# MCUCircuit.net
KiCad netlist of a schematic drawn in Altium Designer
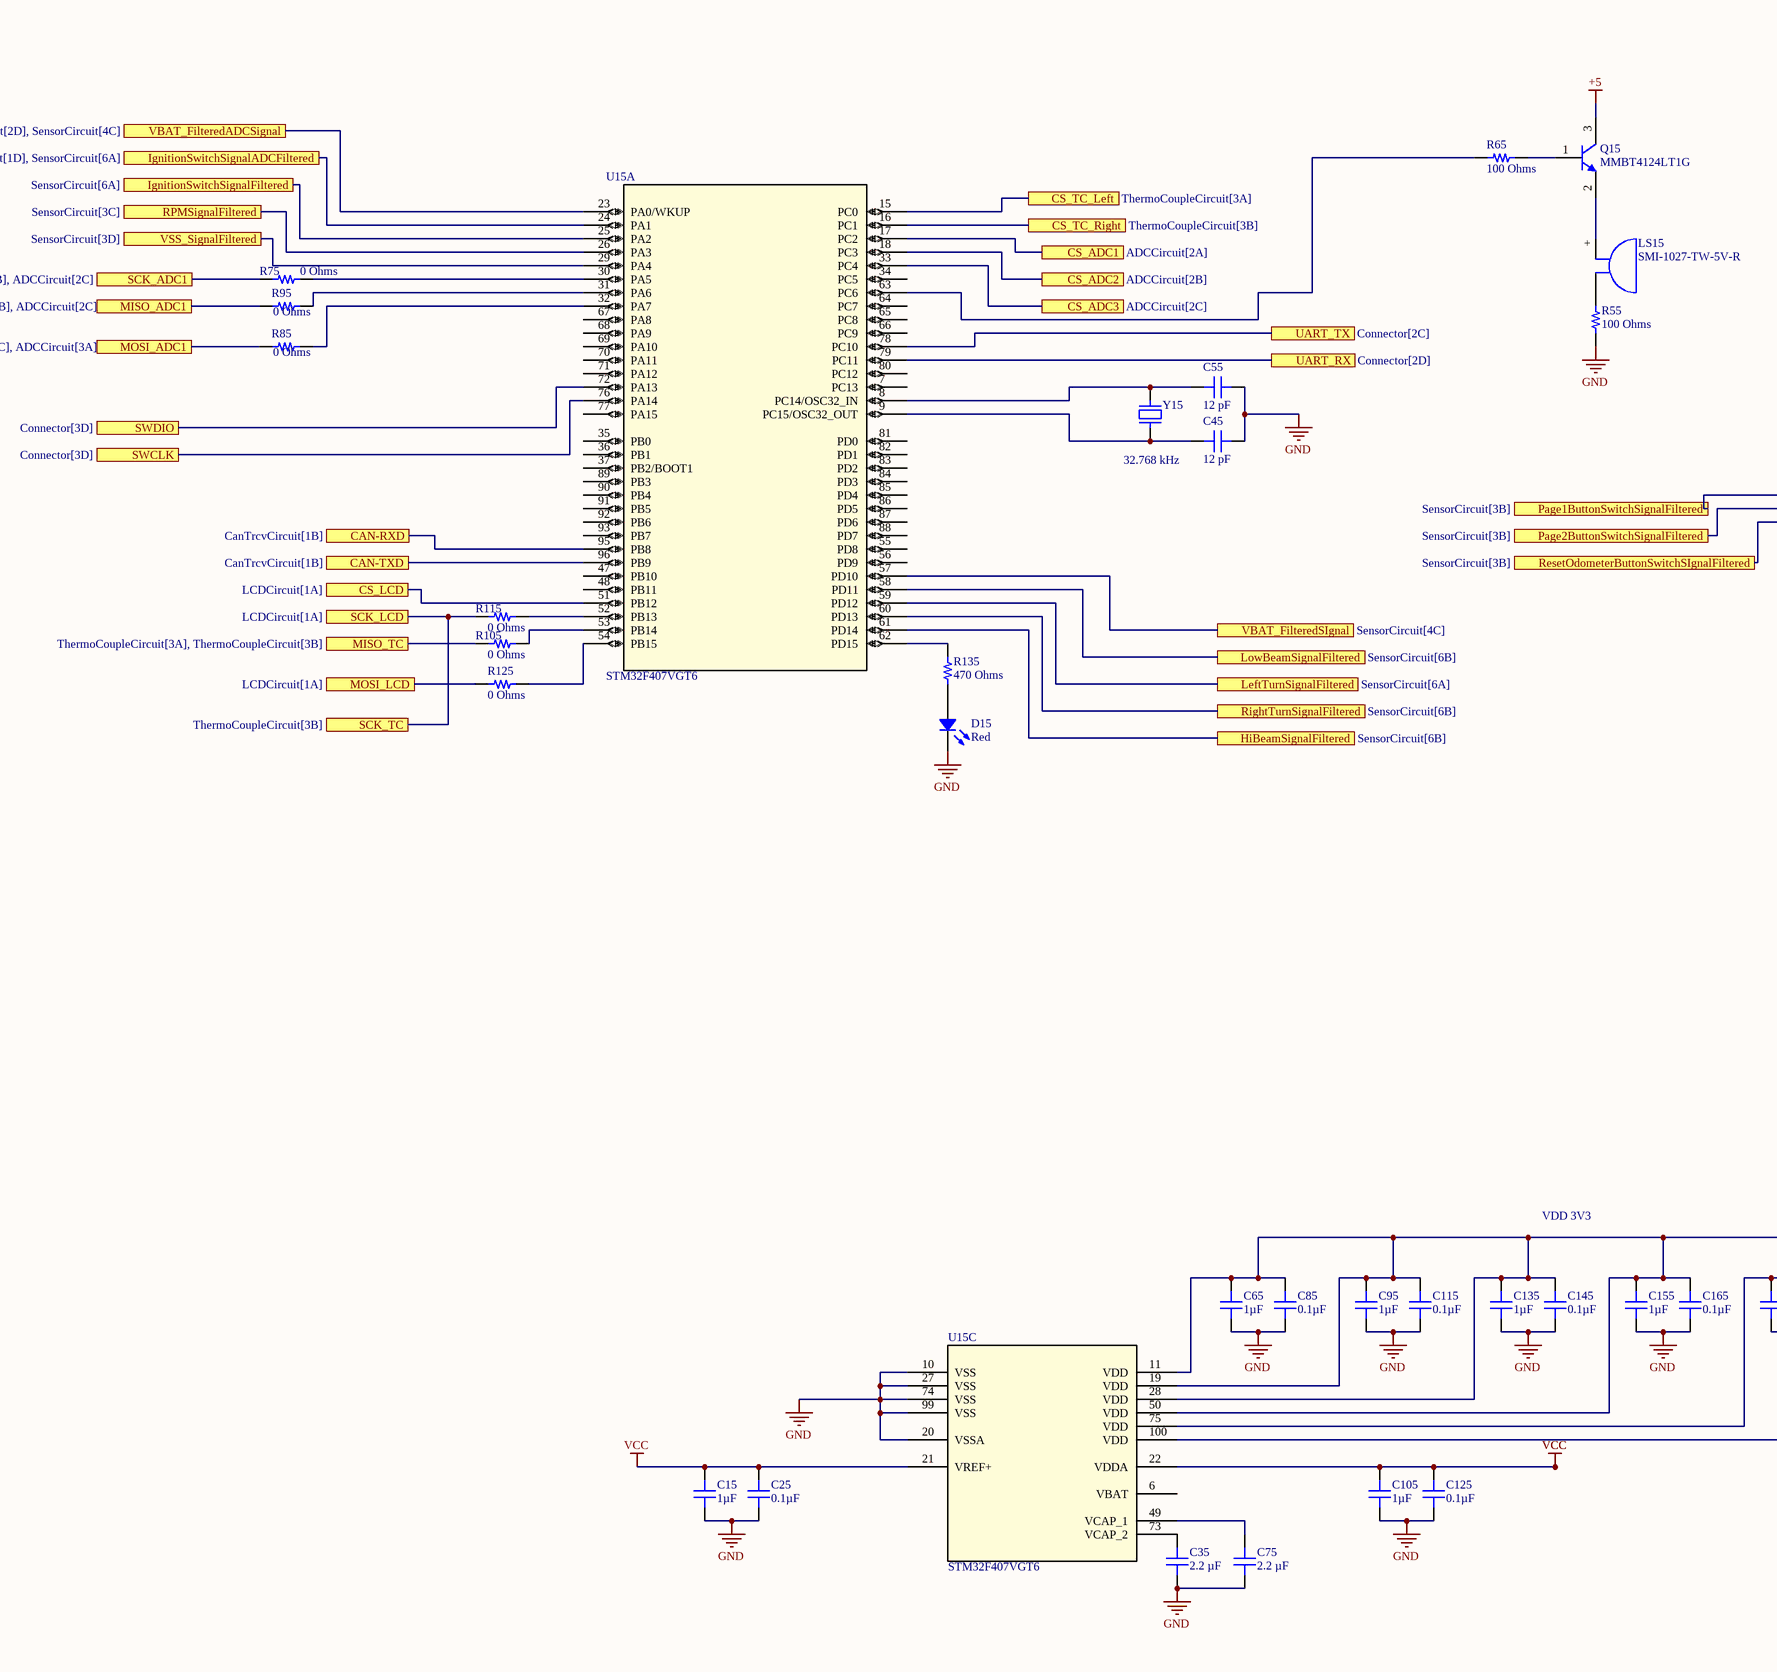
[diagram p0: MCUCircuit.SchDoc, left]
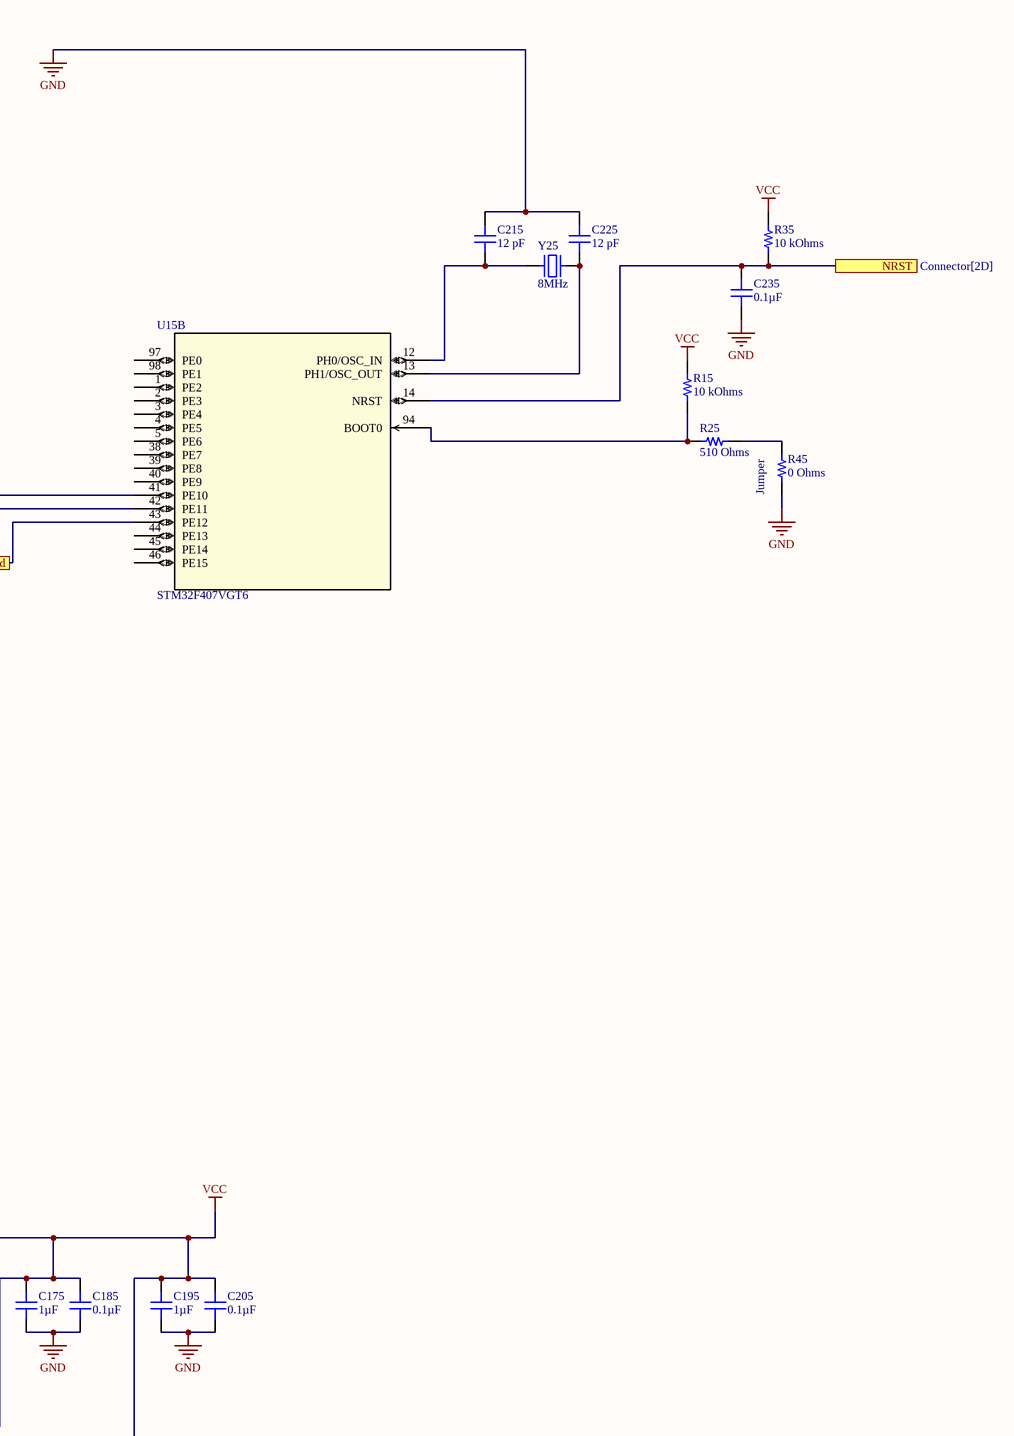
[diagram p1: MCUCircuit.SchDoc, right]

(export (version "E")
  (design (tool "Eeschema 10.0.6"))
  (components
    (comp (ref "C15")
      (value "1µF")
      (footprint "C0805")
      (description "CAP CER 1UF 6.3V X5R 0805")
      (fields (field (name "PART NUMBER") "LGC26D105MAT2S1") (field (name "MANUFACTURER") "AVX Corporation"))
      (libsource (lib "Celestial Altium Library - altium_library") (part "Capacitor"))
    )
    (comp (ref "C25")
      (value "0.1µF")
      (footprint "C0805")
      (description "CAP CER 0.1UF 6.3V X7R 0805")
      (fields (field (name "PART NUMBER") "08056C104JAZ2A") (field (name "MANUFACTURER") "AVX Corporation"))
      (libsource (lib "Celestial Altium Library - altium_library") (part "Capacitor"))
    )
    (comp (ref "C35")
      (value "2.2 µF")
      (footprint "C0805")
      (description "CAP CER 2.2UF 6.3V X5R 0805")
      (fields
        (field (name "PART NUMBER") "VJ0805G225KXYTW1BC")
        (field (name "MANUFACTURER") "Vishay Vitramon")
      )
      (libsource (lib "Celestial Altium Library - altium_library") (part "Capacitor"))
    )
    (comp (ref "C45")
      (value "12 pF")
      (footprint "C0805")
      (description "CAP CER 12PF 10V X8R 0805")
      (fields (field (name "PART NUMBER") "C0805C120J8HAC7800") (field (name "MANUFACTURER") "KEMET"))
      (libsource (lib "Celestial Altium Library - altium_library") (part "Capacitor"))
    )
    (comp (ref "C55")
      (value "12 pF")
      (footprint "C0805")
      (description "CAP CER 12PF 10V X8R 0805")
      (fields (field (name "PART NUMBER") "C0805C120J8HAC7800") (field (name "MANUFACTURER") "KEMET"))
      (libsource (lib "Celestial Altium Library - altium_library") (part "Capacitor"))
    )
    (comp (ref "C65")
      (value "1µF")
      (footprint "C0805")
      (description "CAP CER 1UF 6.3V X5R 0805")
      (fields (field (name "PART NUMBER") "LGC26D105MAT2S1") (field (name "MANUFACTURER") "AVX Corporation"))
      (libsource (lib "Celestial Altium Library - altium_library") (part "Capacitor"))
    )
    (comp (ref "C75")
      (value "2.2 µF")
      (footprint "C0805")
      (description "CAP CER 2.2UF 6.3V X5R 0805")
      (fields
        (field (name "PART NUMBER") "VJ0805G225KXYTW1BC")
        (field (name "MANUFACTURER") "Vishay Vitramon")
      )
      (libsource (lib "Celestial Altium Library - altium_library") (part "Capacitor"))
    )
    (comp (ref "C85")
      (value "0.1µF")
      (footprint "C0805")
      (description "CAP CER 0.1UF 6.3V X7R 0805")
      (fields (field (name "PART NUMBER") "08056C104JAZ2A") (field (name "MANUFACTURER") "AVX Corporation"))
      (libsource (lib "Celestial Altium Library - altium_library") (part "Capacitor"))
    )
    (comp (ref "C95")
      (value "1µF")
      (footprint "C0805")
      (description "CAP CER 1UF 6.3V X5R 0805")
      (fields (field (name "PART NUMBER") "LGC26D105MAT2S1") (field (name "MANUFACTURER") "AVX Corporation"))
      (libsource (lib "Celestial Altium Library - altium_library") (part "Capacitor"))
    )
    (comp (ref "C105")
      (value "1µF")
      (footprint "C0805")
      (description "CAP CER 1UF 6.3V X5R 0805")
      (fields (field (name "PART NUMBER") "LGC26D105MAT2S1") (field (name "MANUFACTURER") "AVX Corporation"))
      (libsource (lib "Celestial Altium Library - altium_library") (part "Capacitor"))
    )
    (comp (ref "C115")
      (value "0.1µF")
      (footprint "C0805")
      (description "CAP CER 0.1UF 6.3V X7R 0805")
      (fields (field (name "PART NUMBER") "08056C104JAZ2A") (field (name "MANUFACTURER") "AVX Corporation"))
      (libsource (lib "Celestial Altium Library - altium_library") (part "Capacitor"))
    )
    (comp (ref "C125")
      (value "0.1µF")
      (footprint "C0805")
      (description "CAP CER 0.1UF 6.3V X7R 0805")
      (fields (field (name "PART NUMBER") "08056C104JAZ2A") (field (name "MANUFACTURER") "AVX Corporation"))
      (libsource (lib "Celestial Altium Library - altium_library") (part "Capacitor"))
    )
    (comp (ref "C135")
      (value "1µF")
      (footprint "C0805")
      (description "CAP CER 1UF 6.3V X5R 0805")
      (fields (field (name "PART NUMBER") "LGC26D105MAT2S1") (field (name "MANUFACTURER") "AVX Corporation"))
      (libsource (lib "Celestial Altium Library - altium_library") (part "Capacitor"))
    )
    (comp (ref "C145")
      (value "0.1µF")
      (footprint "C0805")
      (description "CAP CER 0.1UF 6.3V X7R 0805")
      (fields (field (name "PART NUMBER") "08056C104JAZ2A") (field (name "MANUFACTURER") "AVX Corporation"))
      (libsource (lib "Celestial Altium Library - altium_library") (part "Capacitor"))
    )
    (comp (ref "C155")
      (value "1µF")
      (footprint "C0805")
      (description "CAP CER 1UF 6.3V X5R 0805")
      (fields (field (name "PART NUMBER") "LGC26D105MAT2S1") (field (name "MANUFACTURER") "AVX Corporation"))
      (libsource (lib "Celestial Altium Library - altium_library") (part "Capacitor"))
    )
    (comp (ref "C165")
      (value "0.1µF")
      (footprint "C0805")
      (description "CAP CER 0.1UF 6.3V X7R 0805")
      (fields (field (name "PART NUMBER") "08056C104JAZ2A") (field (name "MANUFACTURER") "AVX Corporation"))
      (libsource (lib "Celestial Altium Library - altium_library") (part "Capacitor"))
    )
    (comp (ref "C175")
      (value "1µF")
      (footprint "C0805")
      (description "CAP CER 1UF 6.3V X5R 0805")
      (fields (field (name "PART NUMBER") "LGC26D105MAT2S1") (field (name "MANUFACTURER") "AVX Corporation"))
      (libsource (lib "Celestial Altium Library - altium_library") (part "Capacitor"))
    )
    (comp (ref "C185")
      (value "0.1µF")
      (footprint "C0805")
      (description "CAP CER 0.1UF 6.3V X7R 0805")
      (fields (field (name "PART NUMBER") "08056C104JAZ2A") (field (name "MANUFACTURER") "AVX Corporation"))
      (libsource (lib "Celestial Altium Library - altium_library") (part "Capacitor"))
    )
    (comp (ref "C195")
      (value "1µF")
      (footprint "C0805")
      (description "CAP CER 1UF 6.3V X5R 0805")
      (fields (field (name "PART NUMBER") "LGC26D105MAT2S1") (field (name "MANUFACTURER") "AVX Corporation"))
      (libsource (lib "Celestial Altium Library - altium_library") (part "Capacitor"))
    )
    (comp (ref "C205")
      (value "0.1µF")
      (footprint "C0805")
      (description "CAP CER 0.1UF 6.3V X7R 0805")
      (fields (field (name "PART NUMBER") "08056C104JAZ2A") (field (name "MANUFACTURER") "AVX Corporation"))
      (libsource (lib "Celestial Altium Library - altium_library") (part "Capacitor"))
    )
    (comp (ref "C215")
      (value "12 pF")
      (footprint "C0805")
      (description "CAP CER 12PF 10V X8R 0805")
      (fields (field (name "PART NUMBER") "C0805C120J8HAC7800") (field (name "MANUFACTURER") "KEMET"))
      (libsource (lib "Celestial Altium Library - altium_library") (part "Capacitor"))
    )
    (comp (ref "C225")
      (value "12 pF")
      (footprint "C0805")
      (description "CAP CER 12PF 10V X8R 0805")
      (fields (field (name "PART NUMBER") "C0805C120J8HAC7800") (field (name "MANUFACTURER") "KEMET"))
      (libsource (lib "Celestial Altium Library - altium_library") (part "Capacitor"))
    )
    (comp (ref "C235")
      (value "0.1µF")
      (footprint "C0805")
      (description "CAP CER 0.1UF 6.3V X7R 0805")
      (fields (field (name "PART NUMBER") "08056C104JAZ2A") (field (name "MANUFACTURER") "AVX Corporation"))
      (libsource (lib "Celestial Altium Library - altium_library") (part "Capacitor"))
    )
    (comp (ref "D15")
      (value "Red")
      (footprint "LED 1206_3216 RED")
      (description "LED RED CLEAR 1206 SMD")
      (fields
        (field (name "PART NUMBER") "25-21/R6C-BR2S2B/2A")
        (field (name "MANUFACTURER") "Everlight Electronics Co Ltd")
      )
      (libsource (lib "Celestial Altium Library - altium_library") (part "LED"))
    )
    (comp (ref "LS15")
      (value "SMI-1027-TW-5V-R")
      (footprint "PUI Audio SMI-1027-TW-5V-R")
      (description "AUDIO MAGNETIC IND 4-7V SMD")
      (fields (field (name "MANUFACTURER") "PUI Audio, Inc."))
      (libsource (lib "Celestial Altium Library - altium_library") (part "Buzzer 2 pin"))
    )
    (comp (ref "Q15")
      (value "MMBT4124LT1G")
      (footprint "ON SEMI SOT-23-3")
      (description "TRANS NPN 25V 0.2A SOT23-3")
      (fields (field (name "MANUFACTURER") "ON Semiconductor"))
      (libsource (lib "Celestial Altium Library - altium_library") (part "ON SEMI NPN SOT-23-3"))
    )
    (comp (ref "R15")
      (value "10 kOhms")
      (footprint "RES 0805_2012")
      (description "RES SMD 10K OHM 5% 1/8W 0805")
      (fields (field (name "PART NUMBER") "AC0805JR-0710KL") (field (name "MANUFACTURER") "Yageo"))
      (libsource (lib "Celestial Altium Library - altium_library") (part "Resistor"))
    )
    (comp (ref "R25")
      (value "510 Ohms")
      (footprint "RES 0805_2012")
      (description "3430 A2 1% 510R 100PPM 1K RL")
      (fields
        (field (name "PART NUMBER") "3430A2F510RTDF")
        (field (name "MANUFACTURER") "TE Connectivity Passive Product")
      )
      (libsource (lib "Celestial Altium Library - altium_library") (part "Resistor"))
    )
    (comp (ref "R35")
      (value "10 kOhms")
      (footprint "RES 0805_2012")
      (description "RES SMD 10K OHM 5% 1/8W 0805")
      (fields (field (name "PART NUMBER") "AC0805JR-0710KL") (field (name "MANUFACTURER") "Yageo"))
      (libsource (lib "Celestial Altium Library - altium_library") (part "Resistor"))
    )
    (comp (ref "R45")
      (value "0 Ohms")
      (footprint "RES 0805_2012")
      (description "RES SMD 0 OHM JUMPER 1/8W 0805")
      (fields (field (name "PART NUMBER") "AA0805JR-070RL") (field (name "MANUFACTURER") "Yageo"))
      (libsource (lib "Celestial Altium Library - altium_library") (part "Resistor"))
    )
    (comp (ref "R55")
      (value "100 Ohms")
      (footprint "RES 0805_2012")
      (description "RES 100 OHM 1% 1/4W 0805")
      (fields (field (name "PART NUMBER") "AC0805FR-7W100RL") (field (name "MANUFACTURER") "Yageo"))
      (libsource (lib "Celestial Altium Library - altium_library") (part "Resistor"))
    )
    (comp (ref "R65")
      (value "100 Ohms")
      (footprint "RES 0805_2012")
      (description "RES 100 OHM 1% 1/4W 0805")
      (fields (field (name "PART NUMBER") "AC0805FR-7W100RL") (field (name "MANUFACTURER") "Yageo"))
      (libsource (lib "Celestial Altium Library - altium_library") (part "Resistor"))
    )
    (comp (ref "R75")
      (value "0 Ohms")
      (footprint "RES 0805_2012")
      (description "RES 0 OHM JUMPER 0805")
      (fields (field (name "PART NUMBER") "WJC0805LJUMPFNR") (field (name "MANUFACTURER") "Littelfuse Inc."))
      (libsource (lib "Celestial Altium Library - altium_library") (part "Resistor"))
    )
    (comp (ref "R85")
      (value "0 Ohms")
      (footprint "RES 0805_2012")
      (description "RES 0 OHM JUMPER 0805")
      (fields (field (name "PART NUMBER") "WJC0805LJUMPFNR") (field (name "MANUFACTURER") "Littelfuse Inc."))
      (libsource (lib "Celestial Altium Library - altium_library") (part "Resistor"))
    )
    (comp (ref "R95")
      (value "0 Ohms")
      (footprint "RES 0805_2012")
      (description "RES 0 OHM JUMPER 0805")
      (fields (field (name "PART NUMBER") "WJC0805LJUMPFNR") (field (name "MANUFACTURER") "Littelfuse Inc."))
      (libsource (lib "Celestial Altium Library - altium_library") (part "Resistor"))
    )
    (comp (ref "R105")
      (value "0 Ohms")
      (footprint "RES 0805_2012")
      (description "RES 0 OHM JUMPER 0805")
      (fields (field (name "PART NUMBER") "WJC0805LJUMPFNR") (field (name "MANUFACTURER") "Littelfuse Inc."))
      (libsource (lib "Celestial Altium Library - altium_library") (part "Resistor"))
    )
    (comp (ref "R115")
      (value "0 Ohms")
      (footprint "RES 0805_2012")
      (description "RES 0 OHM JUMPER 0805")
      (fields (field (name "PART NUMBER") "WJC0805LJUMPFNR") (field (name "MANUFACTURER") "Littelfuse Inc."))
      (libsource (lib "Celestial Altium Library - altium_library") (part "Resistor"))
    )
    (comp (ref "R125")
      (value "0 Ohms")
      (footprint "RES 0805_2012")
      (description "RES 0 OHM JUMPER 0805")
      (fields (field (name "PART NUMBER") "WJC0805LJUMPFNR") (field (name "MANUFACTURER") "Littelfuse Inc."))
      (libsource (lib "Celestial Altium Library - altium_library") (part "Resistor"))
    )
    (comp (ref "R135")
      (value "470 Ohms")
      (footprint "RES 0805_2012")
      (description "RES 470 OHM 1% 1/4W 0805")
      (fields (field (name "PART NUMBER") "AC0805FR-7W470RL") (field (name "MANUFACTURER") "Yageo"))
      (libsource (lib "Celestial Altium Library - altium_library") (part "Resistor"))
    )
    (comp (ref "U15")
      (value "STM32F407VGT6")
      (footprint "LQFP100-14x14mm")
      (description "No Description Available")
      (libsource (lib "STM32F407VGT6") (part "STM32F407VGT6"))
    )
    (comp (ref "Y15")
      (value "32.768 kHz")
      (footprint "MICRO CRYSTAL CM8V H0.6mm")
      (description "CRYSTAL 32.7680KHZ 12.5PF SMD")
      (fields
        (field (name "PART NUMBER") "CM8V-T1A-32.768KHZ-12.5PF-20PPM-TA-QA")
        (field (name "MANUFACTURER") "Micro Crystal AG")
      )
      (libsource (lib "Celestial Altium Library - altium_library") (part "MICRO CRYSTAL CM8V"))
    )
    (comp (ref "Y25")
      (value "8MHz")
      (footprint "NDK NX8045GB")
      (description "CRYSTAL 8.0000MHZ 8PF SMD")
      (fields
        (field (name "PART NUMBER") "NX8045GB-8.000000MHZ")
        (field (name "MANUFACTURER") "NDK America, Inc.")
      )
      (libsource (lib "Celestial Altium Library - altium_library") (part "NDK Crystal NX8045GB"))
    )
  )
  (nets
    (net (code "1") (name "+5") (class "Default")
      (node (ref "Q15") (pin "3") (pinfunction "C_3") (pintype "passive"))
    )
    (net (code "2") (name "/CAN-RXD") (class "Default")
      (node (ref "U15") (pin "95") (pinfunction "PB8_95") (pintype "bidirectional"))
    )
    (net (code "3") (name "/CAN-TXD") (class "Default")
      (node (ref "U15") (pin "96") (pinfunction "PB9_96") (pintype "bidirectional"))
    )
    (net (code "4") (name "/CS_ADC1") (class "Default")
      (node (ref "U15") (pin "17") (pinfunction "PC2_17") (pintype "bidirectional"))
    )
    (net (code "5") (name "/CS_ADC2") (class "Default")
      (node (ref "U15") (pin "18") (pinfunction "PC3_18") (pintype "bidirectional"))
    )
    (net (code "6") (name "/CS_ADC3") (class "Default")
      (node (ref "U15") (pin "33") (pinfunction "PC4_33") (pintype "bidirectional"))
    )
    (net (code "7") (name "/CS_LCD") (class "Default")
      (node (ref "U15") (pin "51") (pinfunction "PB12_51") (pintype "bidirectional"))
    )
    (net (code "8") (name "/CS_TC_Left") (class "Default")
      (node (ref "U15") (pin "15") (pinfunction "PC0_15") (pintype "bidirectional"))
    )
    (net (code "9") (name "/CS_TC_Right") (class "Default")
      (node (ref "U15") (pin "16") (pinfunction "PC1_16") (pintype "bidirectional"))
    )
    (net (code "10") (name "/HiBeamSignalFiltered") (class "Default")
      (node (ref "U15") (pin "61") (pinfunction "PD14_61") (pintype "bidirectional"))
    )
    (net (code "11") (name "/IgnitionSwitchSignalADCFiltered") (class "Default")
      (node (ref "U15") (pin "24") (pinfunction "PA1_24") (pintype "bidirectional"))
    )
    (net (code "12") (name "/IgnitionSwitchSignalFiltered") (class "Default")
      (node (ref "U15") (pin "25") (pinfunction "PA2_25") (pintype "bidirectional"))
    )
    (net (code "13") (name "/LeftTurnSignalFiltered") (class "Default")
      (node (ref "U15") (pin "59") (pinfunction "PD12_59") (pintype "bidirectional"))
    )
    (net (code "14") (name "/LowBeamSignalFiltered") (class "Default")
      (node (ref "U15") (pin "58") (pinfunction "PD11_58") (pintype "bidirectional"))
    )
    (net (code "15") (name "/MISO_ADC1") (class "Default")
      (node (ref "R95") (pin "1") (pinfunction "1_1") (pintype "passive"))
    )
    (net (code "16") (name "/MISO_TC") (class "Default")
      (node (ref "R105") (pin "1") (pinfunction "1_1") (pintype "passive"))
    )
    (net (code "17") (name "/MOSI_ADC1") (class "Default")
      (node (ref "R85") (pin "1") (pinfunction "1_1") (pintype "passive"))
    )
    (net (code "18") (name "/MOSI_LCD") (class "Default")
      (node (ref "R125") (pin "1") (pinfunction "1_1") (pintype "passive"))
    )
    (net (code "19") (name "/NRST") (class "Default")
      (node (ref "C235") (pin "2") (pinfunction "2_2") (pintype "passive"))
      (node (ref "R35") (pin "1") (pinfunction "1_1") (pintype "passive"))
      (node (ref "U15") (pin "14") (pinfunction "NRST_14") (pintype "bidirectional"))
    )
    (net (code "20") (name "/Page1ButtonSwitchSignalFiltered") (class "Default")
      (node (ref "U15") (pin "41") (pinfunction "PE10_41") (pintype "bidirectional"))
    )
    (net (code "21") (name "/Page2ButtonSwitchSignalFiltered") (class "Default")
      (node (ref "U15") (pin "42") (pinfunction "PE11_42") (pintype "bidirectional"))
    )
    (net (code "22") (name "/RPMSignalFiltered") (class "Default")
      (node (ref "U15") (pin "26") (pinfunction "PA3_26") (pintype "bidirectional"))
    )
    (net (code "23") (name "/ResetOdometerButtonSwitchSIgnalFiltered") (class "Default")
      (node (ref "U15") (pin "43") (pinfunction "PE12_43") (pintype "bidirectional"))
    )
    (net (code "24") (name "/RightTurnSignalFiltered") (class "Default")
      (node (ref "U15") (pin "60") (pinfunction "PD13_60") (pintype "bidirectional"))
    )
    (net (code "25") (name "/SCK_ADC1") (class "Default")
      (node (ref "R75") (pin "1") (pinfunction "1_1") (pintype "passive"))
    )
    (net (code "26") (name "/SCK_LCD") (class "Default")
      (node (ref "R115") (pin "1") (pinfunction "1_1") (pintype "passive"))
    )
    (net (code "27") (name "/SWCLK") (class "Default")
      (node (ref "U15") (pin "76") (pinfunction "PA14_76") (pintype "bidirectional"))
    )
    (net (code "28") (name "/SWDIO") (class "Default")
      (node (ref "U15") (pin "72") (pinfunction "PA13_72") (pintype "bidirectional"))
    )
    (net (code "29") (name "/UART_RX") (class "Default")
      (node (ref "U15") (pin "79") (pinfunction "PC11_79") (pintype "bidirectional"))
    )
    (net (code "30") (name "/UART_TX") (class "Default")
      (node (ref "U15") (pin "78") (pinfunction "PC10_78") (pintype "bidirectional"))
    )
    (net (code "31") (name "/VBAT_FilteredADCSignal") (class "Default")
      (node (ref "U15") (pin "23") (pinfunction "PA0/WKUP_23") (pintype "bidirectional"))
    )
    (net (code "32") (name "/VBAT_FilteredSIgnal") (class "Default")
      (node (ref "U15") (pin "57") (pinfunction "PD10_57") (pintype "bidirectional"))
    )
    (net (code "33") (name "/VSS_SignalFiltered") (class "Default")
      (node (ref "U15") (pin "29") (pinfunction "PA4_29") (pintype "bidirectional"))
    )
    (net (code "34") (name "GND") (class "Default")
      (node (ref "C105") (pin "1") (pinfunction "1_1") (pintype "passive"))
      (node (ref "C115") (pin "1") (pinfunction "1_1") (pintype "passive"))
      (node (ref "C125") (pin "1") (pinfunction "1_1") (pintype "passive"))
      (node (ref "C135") (pin "1") (pinfunction "1_1") (pintype "passive"))
      (node (ref "C145") (pin "1") (pinfunction "1_1") (pintype "passive"))
      (node (ref "C15") (pin "1") (pinfunction "1_1") (pintype "passive"))
      (node (ref "C155") (pin "1") (pinfunction "1_1") (pintype "passive"))
      (node (ref "C165") (pin "1") (pinfunction "1_1") (pintype "passive"))
      (node (ref "C175") (pin "1") (pinfunction "1_1") (pintype "passive"))
      (node (ref "C185") (pin "1") (pinfunction "1_1") (pintype "passive"))
      (node (ref "C195") (pin "1") (pinfunction "1_1") (pintype "passive"))
      (node (ref "C205") (pin "1") (pinfunction "1_1") (pintype "passive"))
      (node (ref "C215") (pin "2") (pinfunction "2_2") (pintype "passive"))
      (node (ref "C225") (pin "2") (pinfunction "2_2") (pintype "passive"))
      (node (ref "C235") (pin "1") (pinfunction "1_1") (pintype "passive"))
      (node (ref "C25") (pin "1") (pinfunction "1_1") (pintype "passive"))
      (node (ref "C35") (pin "2") (pinfunction "2_2") (pintype "passive"))
      (node (ref "C45") (pin "2") (pinfunction "2_2") (pintype "passive"))
      (node (ref "C55") (pin "2") (pinfunction "2_2") (pintype "passive"))
      (node (ref "C65") (pin "1") (pinfunction "1_1") (pintype "passive"))
      (node (ref "C75") (pin "2") (pinfunction "2_2") (pintype "passive"))
      (node (ref "C85") (pin "1") (pinfunction "1_1") (pintype "passive"))
      (node (ref "C95") (pin "1") (pinfunction "1_1") (pintype "passive"))
      (node (ref "D15") (pin "2") (pinfunction "2_2") (pintype "passive"))
      (node (ref "R45") (pin "1") (pinfunction "1_1") (pintype "passive"))
      (node (ref "R55") (pin "1") (pinfunction "1_1") (pintype "passive"))
      (node (ref "U15") (pin "10") (pinfunction "VSS_10") (pintype "power_in"))
      (node (ref "U15") (pin "20") (pinfunction "VSSA_20") (pintype "power_in"))
      (node (ref "U15") (pin "27") (pinfunction "VSS_27") (pintype "power_in"))
      (node (ref "U15") (pin "74") (pinfunction "VSS_74") (pintype "power_in"))
      (node (ref "U15") (pin "99") (pinfunction "VSS_99") (pintype "power_in"))
    )
    (net (code "35") (name "Net-(D15-Pad1)") (class "Default")
      (node (ref "D15") (pin "1") (pinfunction "1_1") (pintype "passive"))
      (node (ref "R135") (pin "1") (pinfunction "1_1") (pintype "passive"))
    )
    (net (code "36") (name "Net-(LS15-Pad-)") (class "Default")
      (node (ref "LS15") (pin "-") (pinfunction "-_-") (pintype "passive"))
      (node (ref "R55") (pin "2") (pinfunction "2_2") (pintype "passive"))
    )
    (net (code "37") (name "Net-(Q15-B)") (class "Default")
      (node (ref "Q15") (pin "1") (pinfunction "B_1") (pintype "passive"))
      (node (ref "R65") (pin "1") (pinfunction "1_1") (pintype "passive"))
    )
    (net (code "38") (name "Net-(Q15-E)") (class "Default")
      (node (ref "LS15") (pin "+") (pinfunction "+_+") (pintype "passive"))
      (node (ref "Q15") (pin "2") (pinfunction "E_2") (pintype "passive"))
    )
    (net (code "39") (name "Net-(R25-Pad2)") (class "Default")
      (node (ref "R25") (pin "2") (pinfunction "2_2") (pintype "passive"))
      (node (ref "R45") (pin "2") (pinfunction "2_2") (pintype "passive"))
    )
    (net (code "40") (name "Net-(U15A-PA5)") (class "Default")
      (node (ref "R75") (pin "2") (pinfunction "2_2") (pintype "passive"))
      (node (ref "U15") (pin "30") (pinfunction "PA5_30") (pintype "bidirectional"))
    )
    (net (code "41") (name "Net-(U15A-PA6)") (class "Default")
      (node (ref "R95") (pin "2") (pinfunction "2_2") (pintype "passive"))
      (node (ref "U15") (pin "31") (pinfunction "PA6_31") (pintype "bidirectional"))
    )
    (net (code "42") (name "Net-(U15A-PA7)") (class "Default")
      (node (ref "R85") (pin "2") (pinfunction "2_2") (pintype "passive"))
      (node (ref "U15") (pin "32") (pinfunction "PA7_32") (pintype "bidirectional"))
    )
    (net (code "43") (name "Net-(U15A-PB13)") (class "Default")
      (node (ref "R115") (pin "2") (pinfunction "2_2") (pintype "passive"))
      (node (ref "U15") (pin "52") (pinfunction "PB13_52") (pintype "bidirectional"))
    )
    (net (code "44") (name "Net-(U15A-PB14)") (class "Default")
      (node (ref "R105") (pin "2") (pinfunction "2_2") (pintype "passive"))
      (node (ref "U15") (pin "53") (pinfunction "PB14_53") (pintype "bidirectional"))
    )
    (net (code "45") (name "Net-(U15A-PB15)") (class "Default")
      (node (ref "R125") (pin "2") (pinfunction "2_2") (pintype "passive"))
      (node (ref "U15") (pin "54") (pinfunction "PB15_54") (pintype "bidirectional"))
    )
    (net (code "46") (name "Net-(U15A-PC6)") (class "Default")
      (node (ref "R65") (pin "2") (pinfunction "2_2") (pintype "passive"))
      (node (ref "U15") (pin "63") (pinfunction "PC6_63") (pintype "bidirectional"))
    )
    (net (code "47") (name "Net-(U15A-PC14{slash}OSC32_IN)") (class "Default")
      (node (ref "C55") (pin "1") (pinfunction "1_1") (pintype "passive"))
      (node (ref "U15") (pin "8") (pinfunction "PC14/OSC32_IN_8") (pintype "bidirectional"))
      (node (ref "Y15") (pin "2") (pinfunction "2_2") (pintype "passive"))
    )
    (net (code "48") (name "Net-(U15A-PC15{slash}OSC32_OUT)") (class "Default")
      (node (ref "C45") (pin "1") (pinfunction "1_1") (pintype "passive"))
      (node (ref "U15") (pin "9") (pinfunction "PC15/OSC32_OUT_9") (pintype "bidirectional"))
      (node (ref "Y15") (pin "1") (pinfunction "1_1") (pintype "passive"))
    )
    (net (code "49") (name "Net-(U15A-PD15)") (class "Default")
      (node (ref "R135") (pin "2") (pinfunction "2_2") (pintype "passive"))
      (node (ref "U15") (pin "62") (pinfunction "PD15_62") (pintype "bidirectional"))
    )
    (net (code "50") (name "Net-(U15B-BOOT0)") (class "Default")
      (node (ref "R15") (pin "1") (pinfunction "1_1") (pintype "passive"))
      (node (ref "R25") (pin "1") (pinfunction "1_1") (pintype "passive"))
      (node (ref "U15") (pin "94") (pinfunction "BOOT0_94") (pintype "input"))
    )
    (net (code "51") (name "Net-(U15B-PH0{slash}OSC_IN)") (class "Default")
      (node (ref "C215") (pin "1") (pinfunction "1_1") (pintype "passive"))
      (node (ref "U15") (pin "12") (pinfunction "PH0/OSC_IN_12") (pintype "bidirectional"))
      (node (ref "Y25") (pin "1") (pinfunction "1_1") (pintype "passive"))
    )
    (net (code "52") (name "Net-(U15B-PH1{slash}OSC_OUT)") (class "Default")
      (node (ref "C225") (pin "1") (pinfunction "1_1") (pintype "passive"))
      (node (ref "U15") (pin "13") (pinfunction "PH1/OSC_OUT_13") (pintype "bidirectional"))
      (node (ref "Y25") (pin "2") (pinfunction "2_2") (pintype "passive"))
    )
    (net (code "53") (name "Net-(U15C-VCAP_1)") (class "Default")
      (node (ref "C75") (pin "1") (pinfunction "1_1") (pintype "passive"))
      (node (ref "U15") (pin "49") (pinfunction "VCAP_1_49") (pintype "power_in"))
    )
    (net (code "54") (name "Net-(U15C-VCAP_2)") (class "Default")
      (node (ref "C35") (pin "1") (pinfunction "1_1") (pintype "passive"))
      (node (ref "U15") (pin "73") (pinfunction "VCAP_2_73") (pintype "power_in"))
    )
    (net (code "55") (name "VCC") (class "Default")
      (node (ref "C105") (pin "2") (pinfunction "2_2") (pintype "passive"))
      (node (ref "C115") (pin "2") (pinfunction "2_2") (pintype "passive"))
      (node (ref "C125") (pin "2") (pinfunction "2_2") (pintype "passive"))
      (node (ref "C135") (pin "2") (pinfunction "2_2") (pintype "passive"))
      (node (ref "C145") (pin "2") (pinfunction "2_2") (pintype "passive"))
      (node (ref "C15") (pin "2") (pinfunction "2_2") (pintype "passive"))
      (node (ref "C155") (pin "2") (pinfunction "2_2") (pintype "passive"))
      (node (ref "C165") (pin "2") (pinfunction "2_2") (pintype "passive"))
      (node (ref "C175") (pin "2") (pinfunction "2_2") (pintype "passive"))
      (node (ref "C185") (pin "2") (pinfunction "2_2") (pintype "passive"))
      (node (ref "C195") (pin "2") (pinfunction "2_2") (pintype "passive"))
      (node (ref "C205") (pin "2") (pinfunction "2_2") (pintype "passive"))
      (node (ref "C25") (pin "2") (pinfunction "2_2") (pintype "passive"))
      (node (ref "C65") (pin "2") (pinfunction "2_2") (pintype "passive"))
      (node (ref "C85") (pin "2") (pinfunction "2_2") (pintype "passive"))
      (node (ref "C95") (pin "2") (pinfunction "2_2") (pintype "passive"))
      (node (ref "R15") (pin "2") (pinfunction "2_2") (pintype "passive"))
      (node (ref "R35") (pin "2") (pinfunction "2_2") (pintype "passive"))
      (node (ref "U15") (pin "100") (pinfunction "VDD_100") (pintype "power_in"))
      (node (ref "U15") (pin "11") (pinfunction "VDD_11") (pintype "power_in"))
      (node (ref "U15") (pin "19") (pinfunction "VDD_19") (pintype "power_in"))
      (node (ref "U15") (pin "21") (pinfunction "VREF+_21") (pintype "power_in"))
      (node (ref "U15") (pin "22") (pinfunction "VDDA_22") (pintype "power_in"))
      (node (ref "U15") (pin "28") (pinfunction "VDD_28") (pintype "power_in"))
      (node (ref "U15") (pin "50") (pinfunction "VDD_50") (pintype "power_in"))
      (node (ref "U15") (pin "75") (pinfunction "VDD_75") (pintype "power_in"))
    )
    (net (code "56") (name "unconnected-(U15A-PA8-Pad67)") (class "Default")
      (node (ref "U15") (pin "67") (pinfunction "PA8_67") (pintype "bidirectional"))
    )
    (net (code "57") (name "unconnected-(U15A-PA9-Pad68)") (class "Default")
      (node (ref "U15") (pin "68") (pinfunction "PA9_68") (pintype "bidirectional"))
    )
    (net (code "58") (name "unconnected-(U15A-PA10-Pad69)") (class "Default")
      (node (ref "U15") (pin "69") (pinfunction "PA10_69") (pintype "bidirectional"))
    )
    (net (code "59") (name "unconnected-(U15A-PA11-Pad70)") (class "Default")
      (node (ref "U15") (pin "70") (pinfunction "PA11_70") (pintype "bidirectional"))
    )
    (net (code "60") (name "unconnected-(U15A-PA12-Pad71)") (class "Default")
      (node (ref "U15") (pin "71") (pinfunction "PA12_71") (pintype "bidirectional"))
    )
    (net (code "61") (name "unconnected-(U15A-PA15-Pad77)") (class "Default")
      (node (ref "U15") (pin "77") (pinfunction "PA15_77") (pintype "bidirectional"))
    )
    (net (code "62") (name "unconnected-(U15A-PB0-Pad35)") (class "Default")
      (node (ref "U15") (pin "35") (pinfunction "PB0_35") (pintype "bidirectional"))
    )
    (net (code "63") (name "unconnected-(U15A-PB1-Pad36)") (class "Default")
      (node (ref "U15") (pin "36") (pinfunction "PB1_36") (pintype "bidirectional"))
    )
    (net (code "64") (name "unconnected-(U15A-PB2{slash}BOOT1-Pad37)") (class "Default")
      (node (ref "U15") (pin "37") (pinfunction "PB2/BOOT1_37") (pintype "bidirectional"))
    )
    (net (code "65") (name "unconnected-(U15A-PB3-Pad89)") (class "Default")
      (node (ref "U15") (pin "89") (pinfunction "PB3_89") (pintype "bidirectional"))
    )
    (net (code "66") (name "unconnected-(U15A-PB4-Pad90)") (class "Default")
      (node (ref "U15") (pin "90") (pinfunction "PB4_90") (pintype "bidirectional"))
    )
    (net (code "67") (name "unconnected-(U15A-PB5-Pad91)") (class "Default")
      (node (ref "U15") (pin "91") (pinfunction "PB5_91") (pintype "bidirectional"))
    )
    (net (code "68") (name "unconnected-(U15A-PB6-Pad92)") (class "Default")
      (node (ref "U15") (pin "92") (pinfunction "PB6_92") (pintype "bidirectional"))
    )
    (net (code "69") (name "unconnected-(U15A-PB7-Pad93)") (class "Default")
      (node (ref "U15") (pin "93") (pinfunction "PB7_93") (pintype "bidirectional"))
    )
    (net (code "70") (name "unconnected-(U15A-PB10-Pad47)") (class "Default")
      (node (ref "U15") (pin "47") (pinfunction "PB10_47") (pintype "bidirectional"))
    )
    (net (code "71") (name "unconnected-(U15A-PB11-Pad48)") (class "Default")
      (node (ref "U15") (pin "48") (pinfunction "PB11_48") (pintype "bidirectional"))
    )
    (net (code "72") (name "unconnected-(U15A-PC5-Pad34)") (class "Default")
      (node (ref "U15") (pin "34") (pinfunction "PC5_34") (pintype "bidirectional"))
    )
    (net (code "73") (name "unconnected-(U15A-PC7-Pad64)") (class "Default")
      (node (ref "U15") (pin "64") (pinfunction "PC7_64") (pintype "bidirectional"))
    )
    (net (code "74") (name "unconnected-(U15A-PC8-Pad65)") (class "Default")
      (node (ref "U15") (pin "65") (pinfunction "PC8_65") (pintype "bidirectional"))
    )
    (net (code "75") (name "unconnected-(U15A-PC9-Pad66)") (class "Default")
      (node (ref "U15") (pin "66") (pinfunction "PC9_66") (pintype "bidirectional"))
    )
    (net (code "76") (name "unconnected-(U15A-PC12-Pad80)") (class "Default")
      (node (ref "U15") (pin "80") (pinfunction "PC12_80") (pintype "bidirectional"))
    )
    (net (code "77") (name "unconnected-(U15A-PC13-Pad7)") (class "Default")
      (node (ref "U15") (pin "7") (pinfunction "PC13_7") (pintype "bidirectional"))
    )
    (net (code "78") (name "unconnected-(U15A-PD0-Pad81)") (class "Default")
      (node (ref "U15") (pin "81") (pinfunction "PD0_81") (pintype "bidirectional"))
    )
    (net (code "79") (name "unconnected-(U15A-PD1-Pad82)") (class "Default")
      (node (ref "U15") (pin "82") (pinfunction "PD1_82") (pintype "bidirectional"))
    )
    (net (code "80") (name "unconnected-(U15A-PD2-Pad83)") (class "Default")
      (node (ref "U15") (pin "83") (pinfunction "PD2_83") (pintype "bidirectional"))
    )
    (net (code "81") (name "unconnected-(U15A-PD3-Pad84)") (class "Default")
      (node (ref "U15") (pin "84") (pinfunction "PD3_84") (pintype "bidirectional"))
    )
    (net (code "82") (name "unconnected-(U15A-PD4-Pad85)") (class "Default")
      (node (ref "U15") (pin "85") (pinfunction "PD4_85") (pintype "bidirectional"))
    )
    (net (code "83") (name "unconnected-(U15A-PD5-Pad86)") (class "Default")
      (node (ref "U15") (pin "86") (pinfunction "PD5_86") (pintype "bidirectional"))
    )
    (net (code "84") (name "unconnected-(U15A-PD6-Pad87)") (class "Default")
      (node (ref "U15") (pin "87") (pinfunction "PD6_87") (pintype "bidirectional"))
    )
    (net (code "85") (name "unconnected-(U15A-PD7-Pad88)") (class "Default")
      (node (ref "U15") (pin "88") (pinfunction "PD7_88") (pintype "bidirectional"))
    )
    (net (code "86") (name "unconnected-(U15A-PD8-Pad55)") (class "Default")
      (node (ref "U15") (pin "55") (pinfunction "PD8_55") (pintype "bidirectional"))
    )
    (net (code "87") (name "unconnected-(U15A-PD9-Pad56)") (class "Default")
      (node (ref "U15") (pin "56") (pinfunction "PD9_56") (pintype "bidirectional"))
    )
    (net (code "88") (name "unconnected-(U15B-PE0-Pad97)") (class "Default")
      (node (ref "U15") (pin "97") (pinfunction "PE0_97") (pintype "bidirectional"))
    )
    (net (code "89") (name "unconnected-(U15B-PE1-Pad98)") (class "Default")
      (node (ref "U15") (pin "98") (pinfunction "PE1_98") (pintype "bidirectional"))
    )
    (net (code "90") (name "unconnected-(U15B-PE2-Pad1)") (class "Default")
      (node (ref "U15") (pin "1") (pinfunction "PE2_1") (pintype "bidirectional"))
    )
    (net (code "91") (name "unconnected-(U15B-PE3-Pad2)") (class "Default")
      (node (ref "U15") (pin "2") (pinfunction "PE3_2") (pintype "bidirectional"))
    )
    (net (code "92") (name "unconnected-(U15B-PE4-Pad3)") (class "Default")
      (node (ref "U15") (pin "3") (pinfunction "PE4_3") (pintype "bidirectional"))
    )
    (net (code "93") (name "unconnected-(U15B-PE5-Pad4)") (class "Default")
      (node (ref "U15") (pin "4") (pinfunction "PE5_4") (pintype "bidirectional"))
    )
    (net (code "94") (name "unconnected-(U15B-PE6-Pad5)") (class "Default")
      (node (ref "U15") (pin "5") (pinfunction "PE6_5") (pintype "bidirectional"))
    )
    (net (code "95") (name "unconnected-(U15B-PE7-Pad38)") (class "Default")
      (node (ref "U15") (pin "38") (pinfunction "PE7_38") (pintype "bidirectional"))
    )
    (net (code "96") (name "unconnected-(U15B-PE8-Pad39)") (class "Default")
      (node (ref "U15") (pin "39") (pinfunction "PE8_39") (pintype "bidirectional"))
    )
    (net (code "97") (name "unconnected-(U15B-PE9-Pad40)") (class "Default")
      (node (ref "U15") (pin "40") (pinfunction "PE9_40") (pintype "bidirectional"))
    )
    (net (code "98") (name "unconnected-(U15B-PE13-Pad44)") (class "Default")
      (node (ref "U15") (pin "44") (pinfunction "PE13_44") (pintype "bidirectional"))
    )
    (net (code "99") (name "unconnected-(U15B-PE14-Pad45)") (class "Default")
      (node (ref "U15") (pin "45") (pinfunction "PE14_45") (pintype "bidirectional"))
    )
    (net (code "100") (name "unconnected-(U15B-PE15-Pad46)") (class "Default")
      (node (ref "U15") (pin "46") (pinfunction "PE15_46") (pintype "bidirectional"))
    )
    (net (code "101") (name "unconnected-(U15C-VBAT-Pad6)") (class "Default")
      (node (ref "U15") (pin "6") (pinfunction "VBAT_6") (pintype "power_in"))
    )
  )
)
